# STM32F030_v1.net
KiCad netlist of a schematic drawn in EAGLE
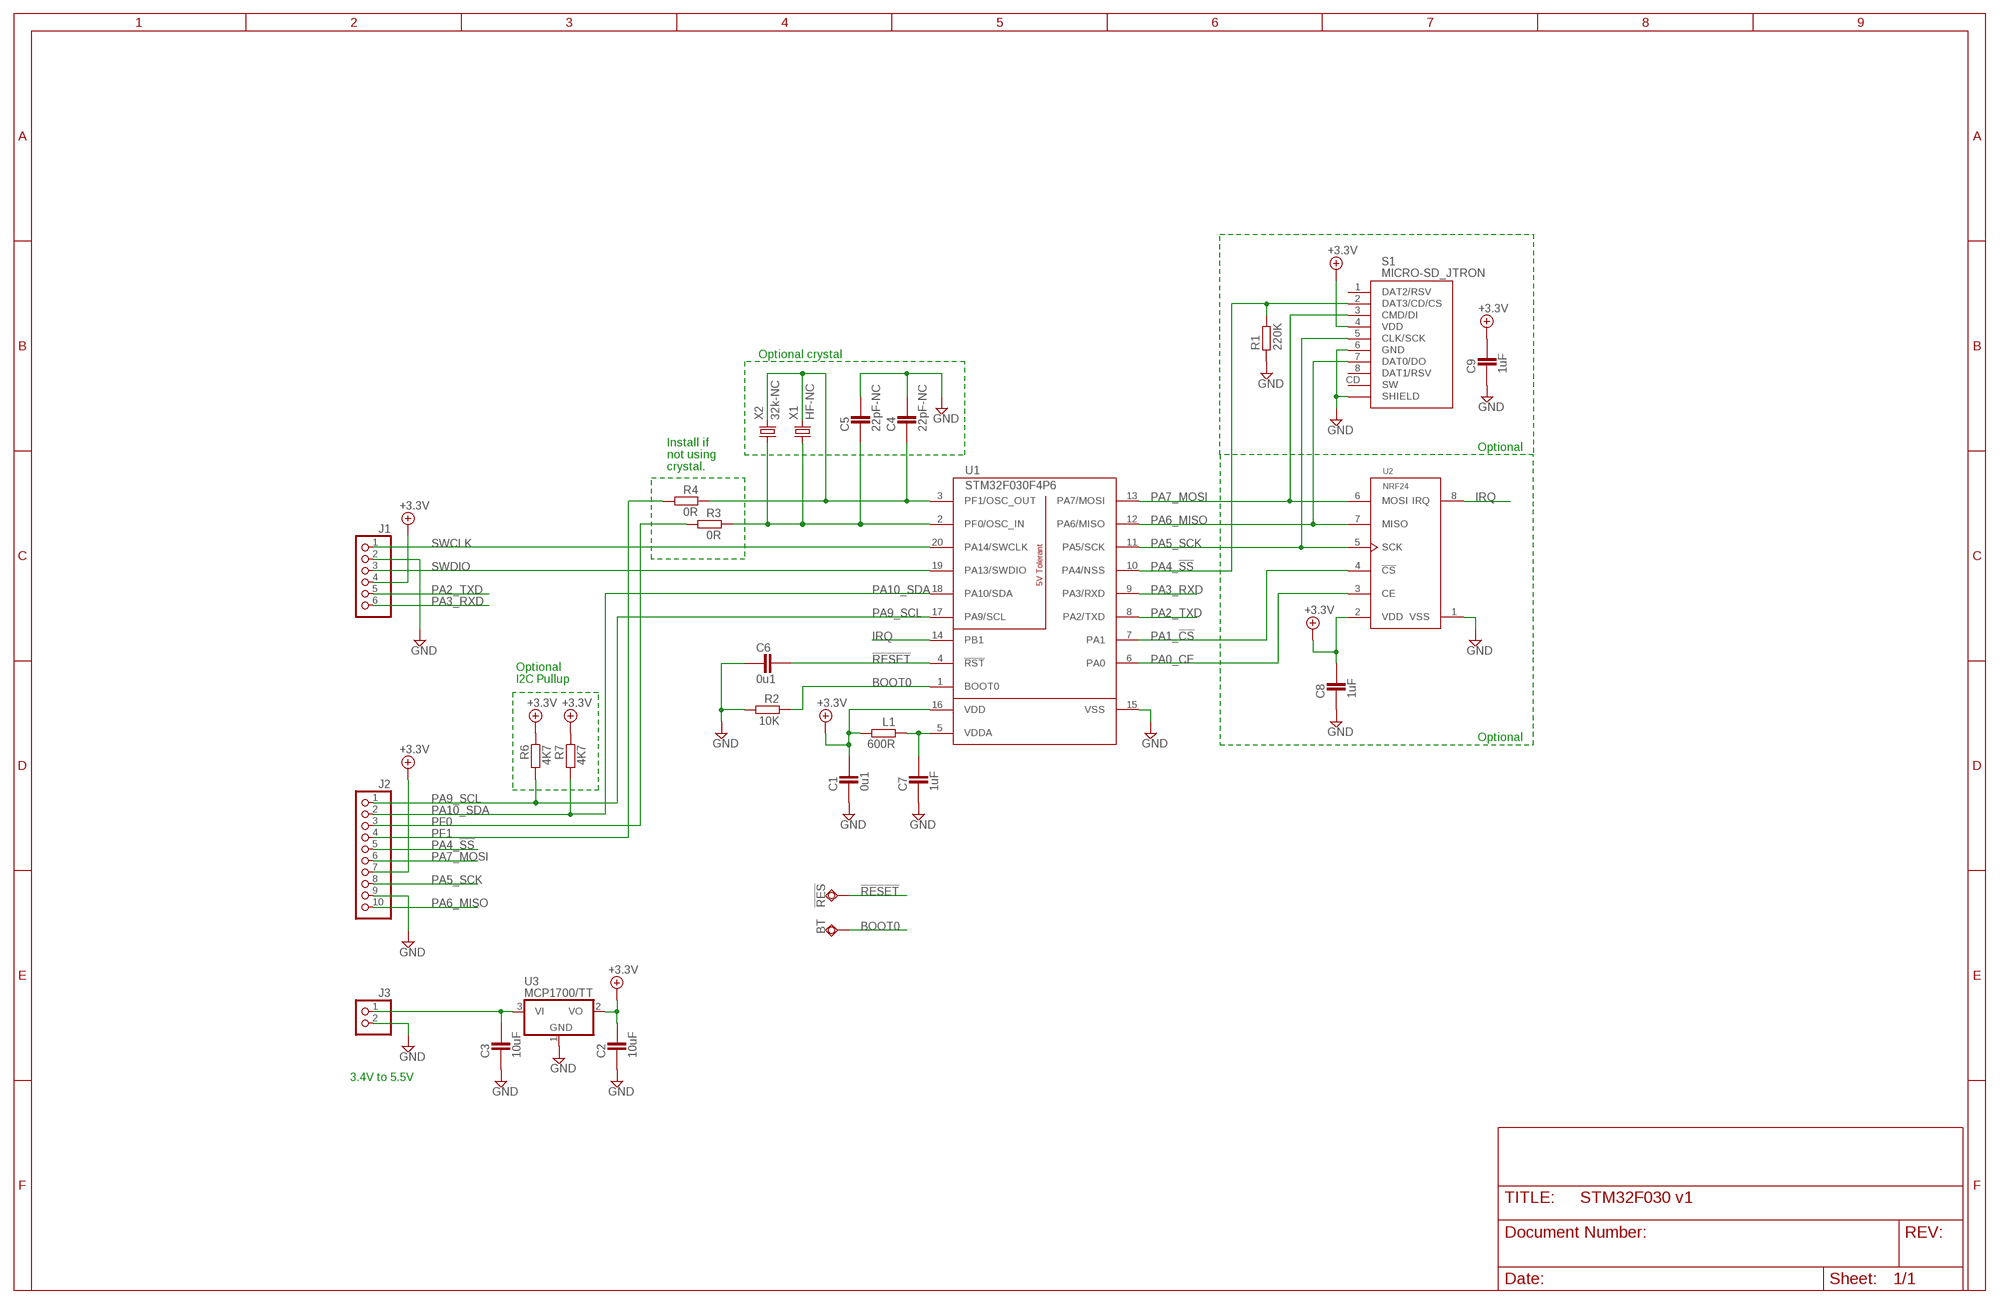
[diagram p0: schematic, sheet 1]

(export (version "E")
  (design (tool "Eeschema 10.0.6"))
  (components
    (comp (ref "!RES")
      (value "TPSQTP08SQ")
      (footprint "eagle-import:TP08SQ")
      (libsource (lib "eagle-import") (part "TPSQTP08SQ"))
    )
    (comp (ref "BT")
      (value "TPSQTP08SQ")
      (footprint "eagle-import:TP08SQ")
      (libsource (lib "eagle-import") (part "TPSQTP08SQ"))
    )
    (comp (ref "C1")
      (value "0u1")
      (footprint "eagle-import:CAPC1608X92N")
      (fields (field (name "PARTNO") "0U1, 0603"))
      (libsource (lib "eagle-import") (part "CAPACITOR_0603"))
    )
    (comp (ref "C2")
      (value "10uF")
      (footprint "eagle-import:CAPC2012X145AN")
      (fields (field (name "PARTNO") "10uF, 0805"))
      (libsource (lib "eagle-import") (part "CAPACITOR_0805"))
    )
    (comp (ref "C3")
      (value "10uF")
      (footprint "eagle-import:CAPC2012X145AN")
      (fields (field (name "PARTNO") "10uF, 0805"))
      (libsource (lib "eagle-import") (part "CAPACITOR_0805"))
    )
    (comp (ref "C4")
      (value "22pF-NC")
      (footprint "eagle-import:CAPC1608X92N")
      (fields (field (name "PARTNO") "22PF, 0603"))
      (libsource (lib "eagle-import") (part "CAPACITOR_0603"))
    )
    (comp (ref "C5")
      (value "22pF-NC")
      (footprint "eagle-import:CAPC1608X92N")
      (fields (field (name "PARTNO") "22PF, 0603"))
      (libsource (lib "eagle-import") (part "CAPACITOR_0603"))
    )
    (comp (ref "C6")
      (value "0u1")
      (footprint "eagle-import:CAPC1608X92N")
      (fields (field (name "PARTNO") "0U1, 0603"))
      (libsource (lib "eagle-import") (part "CAPACITOR_0603"))
    )
    (comp (ref "C7")
      (value "1uF")
      (footprint "eagle-import:CAPC1608X92N")
      (fields (field (name "PARTNO") "1UF, 0603"))
      (libsource (lib "eagle-import") (part "CAPACITOR_0603"))
    )
    (comp (ref "C8")
      (value "1uF")
      (footprint "eagle-import:CAPC1608X92N")
      (fields (field (name "PARTNO") "1UF, 0603"))
      (libsource (lib "eagle-import") (part "CAPACITOR_0603"))
    )
    (comp (ref "C9")
      (value "1uF")
      (footprint "eagle-import:CAPC1608X92N")
      (fields (field (name "PARTNO") "1UF, 0603"))
      (libsource (lib "eagle-import") (part "CAPACITOR_0603"))
    )
    (comp (ref "J1")
      (value "PINHD-1X6")
      (footprint "eagle-import:1X06")
      (fields (field (name "PARTNO") "HEADER 1X6"))
      (libsource (lib "eagle-import") (part "PINHD-1X6"))
    )
    (comp (ref "J2")
      (value "PINHD-1X10")
      (footprint "eagle-import:1X10")
      (fields (field (name "PARTNO") "HEADER 1X10"))
      (libsource (lib "eagle-import") (part "PINHD-1X10"))
    )
    (comp (ref "J3")
      (value "PINHD-1X2_2.54")
      (footprint "eagle-import:1X02")
      (fields (field (name "PARTNO") "HEADER 1X2"))
      (libsource (lib "eagle-import") (part "PINHD-1X2_2.54"))
    )
    (comp (ref "L1")
      (value "600R")
      (footprint "eagle-import:RESC1608X55N")
      (fields (field (name "PARTNO") "FERRITE 0603 600R 0.2A"))
      (libsource (lib "eagle-import") (part "RESISTOR_0603"))
    )
    (comp (ref "R1")
      (value "220K")
      (footprint "eagle-import:RESC1608X55N")
      (fields (field (name "PARTNO") "220K, 0603"))
      (libsource (lib "eagle-import") (part "RESISTOR_0603"))
    )
    (comp (ref "R2")
      (value "10K")
      (footprint "eagle-import:RESC1608X55N")
      (fields (field (name "PARTNO") "10K, 0603"))
      (libsource (lib "eagle-import") (part "RESISTOR_0603"))
    )
    (comp (ref "R3")
      (value "0R")
      (footprint "eagle-import:RESC1608X55N")
      (fields (field (name "PARTNO") "0R, 0603"))
      (libsource (lib "eagle-import") (part "RESISTOR_0603"))
    )
    (comp (ref "R4")
      (value "0R")
      (footprint "eagle-import:RESC1608X55N")
      (fields (field (name "PARTNO") "0R, 0603"))
      (libsource (lib "eagle-import") (part "RESISTOR_0603"))
    )
    (comp (ref "R6")
      (value "4K7")
      (footprint "eagle-import:RESC1608X55N")
      (fields (field (name "PARTNO") "4K7, 0603"))
      (libsource (lib "eagle-import") (part "RESISTOR_0603"))
    )
    (comp (ref "R7")
      (value "4K7")
      (footprint "eagle-import:RESC1608X55N")
      (fields (field (name "PARTNO") "4K7, 0603"))
      (libsource (lib "eagle-import") (part "RESISTOR_0603"))
    )
    (comp (ref "S1")
      (value "MICRO-SD_JTRON")
      (footprint "eagle-import:JTRON-MICROSD")
      (fields (field (name "PARTNO") "JTRON MICROSD SOCKET"))
      (libsource (lib "eagle-import") (part "MICRO-SD_JTRON"))
    )
    (comp (ref "U1")
      (value "STM32F030F4P6")
      (footprint "eagle-import:TSSOP20")
      (libsource (lib "eagle-import") (part "STM32F030F4P6"))
    )
    (comp (ref "U2")
      (value "NRF24")
      (footprint "eagle-import:NRF24L01")
      (fields (field (name "PARTNO") "NRF24L01+ MODULE"))
      (libsource (lib "eagle-import") (part "NRF24"))
    )
    (comp (ref "U3")
      (value "MCP1700/TT")
      (footprint "eagle-import:SOT95P280X135-3N")
      (fields (field (name "PARTNO") "MCP1700T-3302E/TT"))
      (libsource (lib "eagle-import") (part "MCP1700/TT"))
    )
    (comp (ref "X1")
      (value "HF-NC")
      (footprint "eagle-import:SM49")
      (fields (field (name "PARTNO") "12MHZ, HC49/US"))
      (libsource (lib "eagle-import") (part "CRYSTALSM49"))
    )
    (comp (ref "X2")
      (value "32k-NC")
      (footprint "eagle-import:CRYSTAL32SMT")
      (fields (field (name "PARTNO") "32.768KHZ"))
      (libsource (lib "eagle-import") (part "CRYSTALWATCH"))
    )
  )
  (nets
    (net (code "1") (name "+3.3V") (class "Default")
      (node (ref "C1") (pin "2") (pinfunction "2_2") (pintype "passive"))
      (node (ref "C2") (pin "2") (pinfunction "2_2") (pintype "passive"))
      (node (ref "C8") (pin "2") (pinfunction "2_2") (pintype "passive"))
      (node (ref "C9") (pin "2") (pinfunction "2_2") (pintype "passive"))
      (node (ref "J1") (pin "4") (pinfunction "4_4") (pintype "passive"))
      (node (ref "J2") (pin "7") (pinfunction "7_7") (pintype "passive"))
      (node (ref "L1") (pin "2") (pinfunction "2_2") (pintype "passive"))
      (node (ref "R6") (pin "1") (pinfunction "1_1") (pintype "passive"))
      (node (ref "R7") (pin "1") (pinfunction "1_1") (pintype "passive"))
      (node (ref "S1") (pin "4") (pinfunction "VDD_4") (pintype "bidirectional"))
      (node (ref "U1") (pin "16") (pinfunction "VDD_16") (pintype "input"))
      (node (ref "U2") (pin "2") (pinfunction "VDD_2") (pintype "input"))
      (node (ref "U3") (pin "2") (pinfunction "VO_2") (pintype "passive"))
    )
    (net (code "2") (name "/BOOT0") (class "Default")
      (node (ref "BT") (pin "TP") (pinfunction "TP_TP") (pintype "input"))
      (node (ref "R2") (pin "1") (pinfunction "1_1") (pintype "passive"))
      (node (ref "U1") (pin "1") (pinfunction "BOOT0_1") (pintype "input"))
    )
    (net (code "3") (name "/IRQ") (class "Default")
      (node (ref "U1") (pin "14") (pinfunction "PB1_14") (pintype "bidirectional"))
      (node (ref "U2") (pin "8") (pinfunction "IRQ_8") (pintype "output"))
    )
    (net (code "5") (name "/PA0_CE") (class "Default")
      (node (ref "U1") (pin "6") (pinfunction "PA0_6") (pintype "bidirectional"))
      (node (ref "U2") (pin "3") (pinfunction "CE_3") (pintype "input"))
    )
    (net (code "6") (name "/PA1_~{CS}") (class "Default")
      (node (ref "U1") (pin "7") (pinfunction "PA1_7") (pintype "bidirectional"))
      (node (ref "U2") (pin "4") (pinfunction "~{CS}_4") (pintype "input"))
    )
    (net (code "7") (name "/PA2_TXD") (class "Default")
      (node (ref "J1") (pin "5") (pinfunction "5_5") (pintype "passive"))
      (node (ref "U1") (pin "8") (pinfunction "PA2/TXD_8") (pintype "bidirectional"))
    )
    (net (code "8") (name "/PA3_RXD") (class "Default")
      (node (ref "J1") (pin "6") (pinfunction "6_6") (pintype "passive"))
      (node (ref "U1") (pin "9") (pinfunction "PA3/RXD_9") (pintype "bidirectional"))
    )
    (net (code "9") (name "/PA4_~{SS}") (class "Default")
      (node (ref "J2") (pin "5") (pinfunction "5_5") (pintype "passive"))
      (node (ref "R1") (pin "2") (pinfunction "2_2") (pintype "passive"))
      (node (ref "S1") (pin "2") (pinfunction "DAT3/CD/CS_2") (pintype "bidirectional"))
      (node (ref "U1") (pin "10") (pinfunction "PA4/NSS_10") (pintype "bidirectional"))
    )
    (net (code "10") (name "/PA5_SCK") (class "Default")
      (node (ref "J2") (pin "8") (pinfunction "8_8") (pintype "passive"))
      (node (ref "S1") (pin "5") (pinfunction "CLK/SCK_5") (pintype "bidirectional"))
      (node (ref "U1") (pin "11") (pinfunction "PA5/SCK_11") (pintype "bidirectional"))
      (node (ref "U2") (pin "5") (pinfunction "SCK_5") (pintype "input"))
    )
    (net (code "11") (name "/PA6_MISO") (class "Default")
      (node (ref "J2") (pin "10") (pinfunction "10_10") (pintype "passive"))
      (node (ref "S1") (pin "7") (pinfunction "DAT0/DO_7") (pintype "bidirectional"))
      (node (ref "U1") (pin "12") (pinfunction "PA6/MISO_12") (pintype "bidirectional"))
      (node (ref "U2") (pin "7") (pinfunction "MISO_7") (pintype "output"))
    )
    (net (code "12") (name "/PA7_MOSI") (class "Default")
      (node (ref "J2") (pin "6") (pinfunction "6_6") (pintype "passive"))
      (node (ref "S1") (pin "3") (pinfunction "CMD/DI_3") (pintype "bidirectional"))
      (node (ref "U1") (pin "13") (pinfunction "PA7/MOSI_13") (pintype "bidirectional"))
      (node (ref "U2") (pin "6") (pinfunction "MOSI_6") (pintype "input"))
    )
    (net (code "13") (name "/PA9_SCL") (class "Default")
      (node (ref "J2") (pin "1") (pinfunction "1_1") (pintype "passive"))
      (node (ref "R6") (pin "2") (pinfunction "2_2") (pintype "passive"))
      (node (ref "U1") (pin "17") (pinfunction "PA9/SCL_17") (pintype "bidirectional"))
    )
    (net (code "14") (name "/PA10_SDA") (class "Default")
      (node (ref "J2") (pin "2") (pinfunction "2_2") (pintype "passive"))
      (node (ref "R7") (pin "2") (pinfunction "2_2") (pintype "passive"))
      (node (ref "U1") (pin "18") (pinfunction "PA10/SDA_18") (pintype "bidirectional"))
    )
    (net (code "15") (name "/PF0") (class "Default")
      (node (ref "J2") (pin "3") (pinfunction "3_3") (pintype "passive"))
      (node (ref "R3") (pin "2") (pinfunction "2_2") (pintype "passive"))
    )
    (net (code "16") (name "/PF1") (class "Default")
      (node (ref "J2") (pin "4") (pinfunction "4_4") (pintype "passive"))
      (node (ref "R4") (pin "2") (pinfunction "2_2") (pintype "passive"))
    )
    (net (code "17") (name "/SWCLK") (class "Default")
      (node (ref "J1") (pin "1") (pinfunction "1_1") (pintype "passive"))
      (node (ref "U1") (pin "20") (pinfunction "PA14/SWCLK_20") (pintype "bidirectional"))
    )
    (net (code "18") (name "/SWDIO") (class "Default")
      (node (ref "J1") (pin "3") (pinfunction "3_3") (pintype "passive"))
      (node (ref "U1") (pin "19") (pinfunction "PA13/SWDIO_19") (pintype "bidirectional"))
    )
    (net (code "19") (name "/~{RESET}") (class "Default")
      (node (ref "!RES") (pin "TP") (pinfunction "TP_TP") (pintype "input"))
      (node (ref "C6") (pin "2") (pinfunction "2_2") (pintype "passive"))
      (node (ref "U1") (pin "4") (pinfunction "~{RST}_4") (pintype "input"))
    )
    (net (code "20") (name "GND") (class "Default")
      (node (ref "C1") (pin "1") (pinfunction "1_1") (pintype "passive"))
      (node (ref "C2") (pin "1") (pinfunction "1_1") (pintype "passive"))
      (node (ref "C3") (pin "1") (pinfunction "1_1") (pintype "passive"))
      (node (ref "C4") (pin "2") (pinfunction "2_2") (pintype "passive"))
      (node (ref "C5") (pin "2") (pinfunction "2_2") (pintype "passive"))
      (node (ref "C6") (pin "1") (pinfunction "1_1") (pintype "passive"))
      (node (ref "C7") (pin "1") (pinfunction "1_1") (pintype "passive"))
      (node (ref "C8") (pin "1") (pinfunction "1_1") (pintype "passive"))
      (node (ref "C9") (pin "1") (pinfunction "1_1") (pintype "passive"))
      (node (ref "J1") (pin "2") (pinfunction "2_2") (pintype "passive"))
      (node (ref "J2") (pin "9") (pinfunction "9_9") (pintype "passive"))
      (node (ref "J3") (pin "2") (pinfunction "2_2") (pintype "passive"))
      (node (ref "R1") (pin "1") (pinfunction "1_1") (pintype "passive"))
      (node (ref "R2") (pin "2") (pinfunction "2_2") (pintype "passive"))
      (node (ref "S1") (pin "6") (pinfunction "GND_6") (pintype "bidirectional"))
      (node (ref "S1") (pin "SHIELD@1") (pinfunction "SHIELD_SHIELD@1") (pintype "bidirectional"))
      (node (ref "S1") (pin "SHIELD@2") (pinfunction "SHIELD_SHIELD@2") (pintype "bidirectional"))
      (node (ref "S1") (pin "SHIELD@3") (pinfunction "SHIELD_SHIELD@3") (pintype "bidirectional"))
      (node (ref "S1") (pin "SHIELD@4") (pinfunction "SHIELD_SHIELD@4") (pintype "bidirectional"))
      (node (ref "U1") (pin "15") (pinfunction "VSS_15") (pintype "input"))
      (node (ref "U2") (pin "1") (pinfunction "VSS_1") (pintype "input"))
      (node (ref "U3") (pin "1") (pinfunction "GND_1") (pintype "passive"))
    )
    (net (code "21") (name "Net-(U1-PF0{slash}OSC_IN)") (class "Default")
      (node (ref "C5") (pin "1") (pinfunction "1_1") (pintype "passive"))
      (node (ref "R3") (pin "1") (pinfunction "1_1") (pintype "passive"))
      (node (ref "U1") (pin "2") (pinfunction "PF0/OSC_IN_2") (pintype "input"))
      (node (ref "X1") (pin "1") (pinfunction "1_1") (pintype "passive"))
      (node (ref "X2") (pin "1") (pinfunction "1_1") (pintype "passive"))
    )
    (net (code "22") (name "Net-(U1-PF1{slash}OSC_OUT)") (class "Default")
      (node (ref "C4") (pin "1") (pinfunction "1_1") (pintype "passive"))
      (node (ref "R4") (pin "1") (pinfunction "1_1") (pintype "passive"))
      (node (ref "U1") (pin "3") (pinfunction "PF1/OSC_OUT_3") (pintype "output"))
      (node (ref "X1") (pin "2") (pinfunction "2_2") (pintype "passive"))
      (node (ref "X2") (pin "2") (pinfunction "2_2") (pintype "passive"))
    )
    (net (code "23") (name "Net-(U1-VDDA)") (class "Default")
      (node (ref "C7") (pin "2") (pinfunction "2_2") (pintype "passive"))
      (node (ref "L1") (pin "1") (pinfunction "1_1") (pintype "passive"))
      (node (ref "U1") (pin "5") (pinfunction "VDDA_5") (pintype "input"))
    )
    (net (code "24") (name "Net-(U3-VI)") (class "Default")
      (node (ref "C3") (pin "2") (pinfunction "2_2") (pintype "passive"))
      (node (ref "J3") (pin "1") (pinfunction "1_1") (pintype "passive"))
      (node (ref "U3") (pin "3") (pinfunction "VI_3") (pintype "input"))
    )
    (net (code "25") (name "unconnected-(S1-DAT1{slash}RSV-Pad8)") (class "Default")
      (node (ref "S1") (pin "8") (pinfunction "DAT1/RSV_8") (pintype "bidirectional"))
    )
    (net (code "26") (name "unconnected-(S1-DAT2{slash}RSV-Pad1)") (class "Default")
      (node (ref "S1") (pin "1") (pinfunction "DAT2/RSV_1") (pintype "bidirectional"))
    )
    (net (code "27") (name "unconnected-(S1-SW-PadCD)") (class "Default")
      (node (ref "S1") (pin "CD") (pinfunction "SW_CD") (pintype "bidirectional"))
    )
  )
)
